# Tiny817_Xplained_Pro_EDBG.net
KiCad netlist of a schematic drawn in Altium Designer
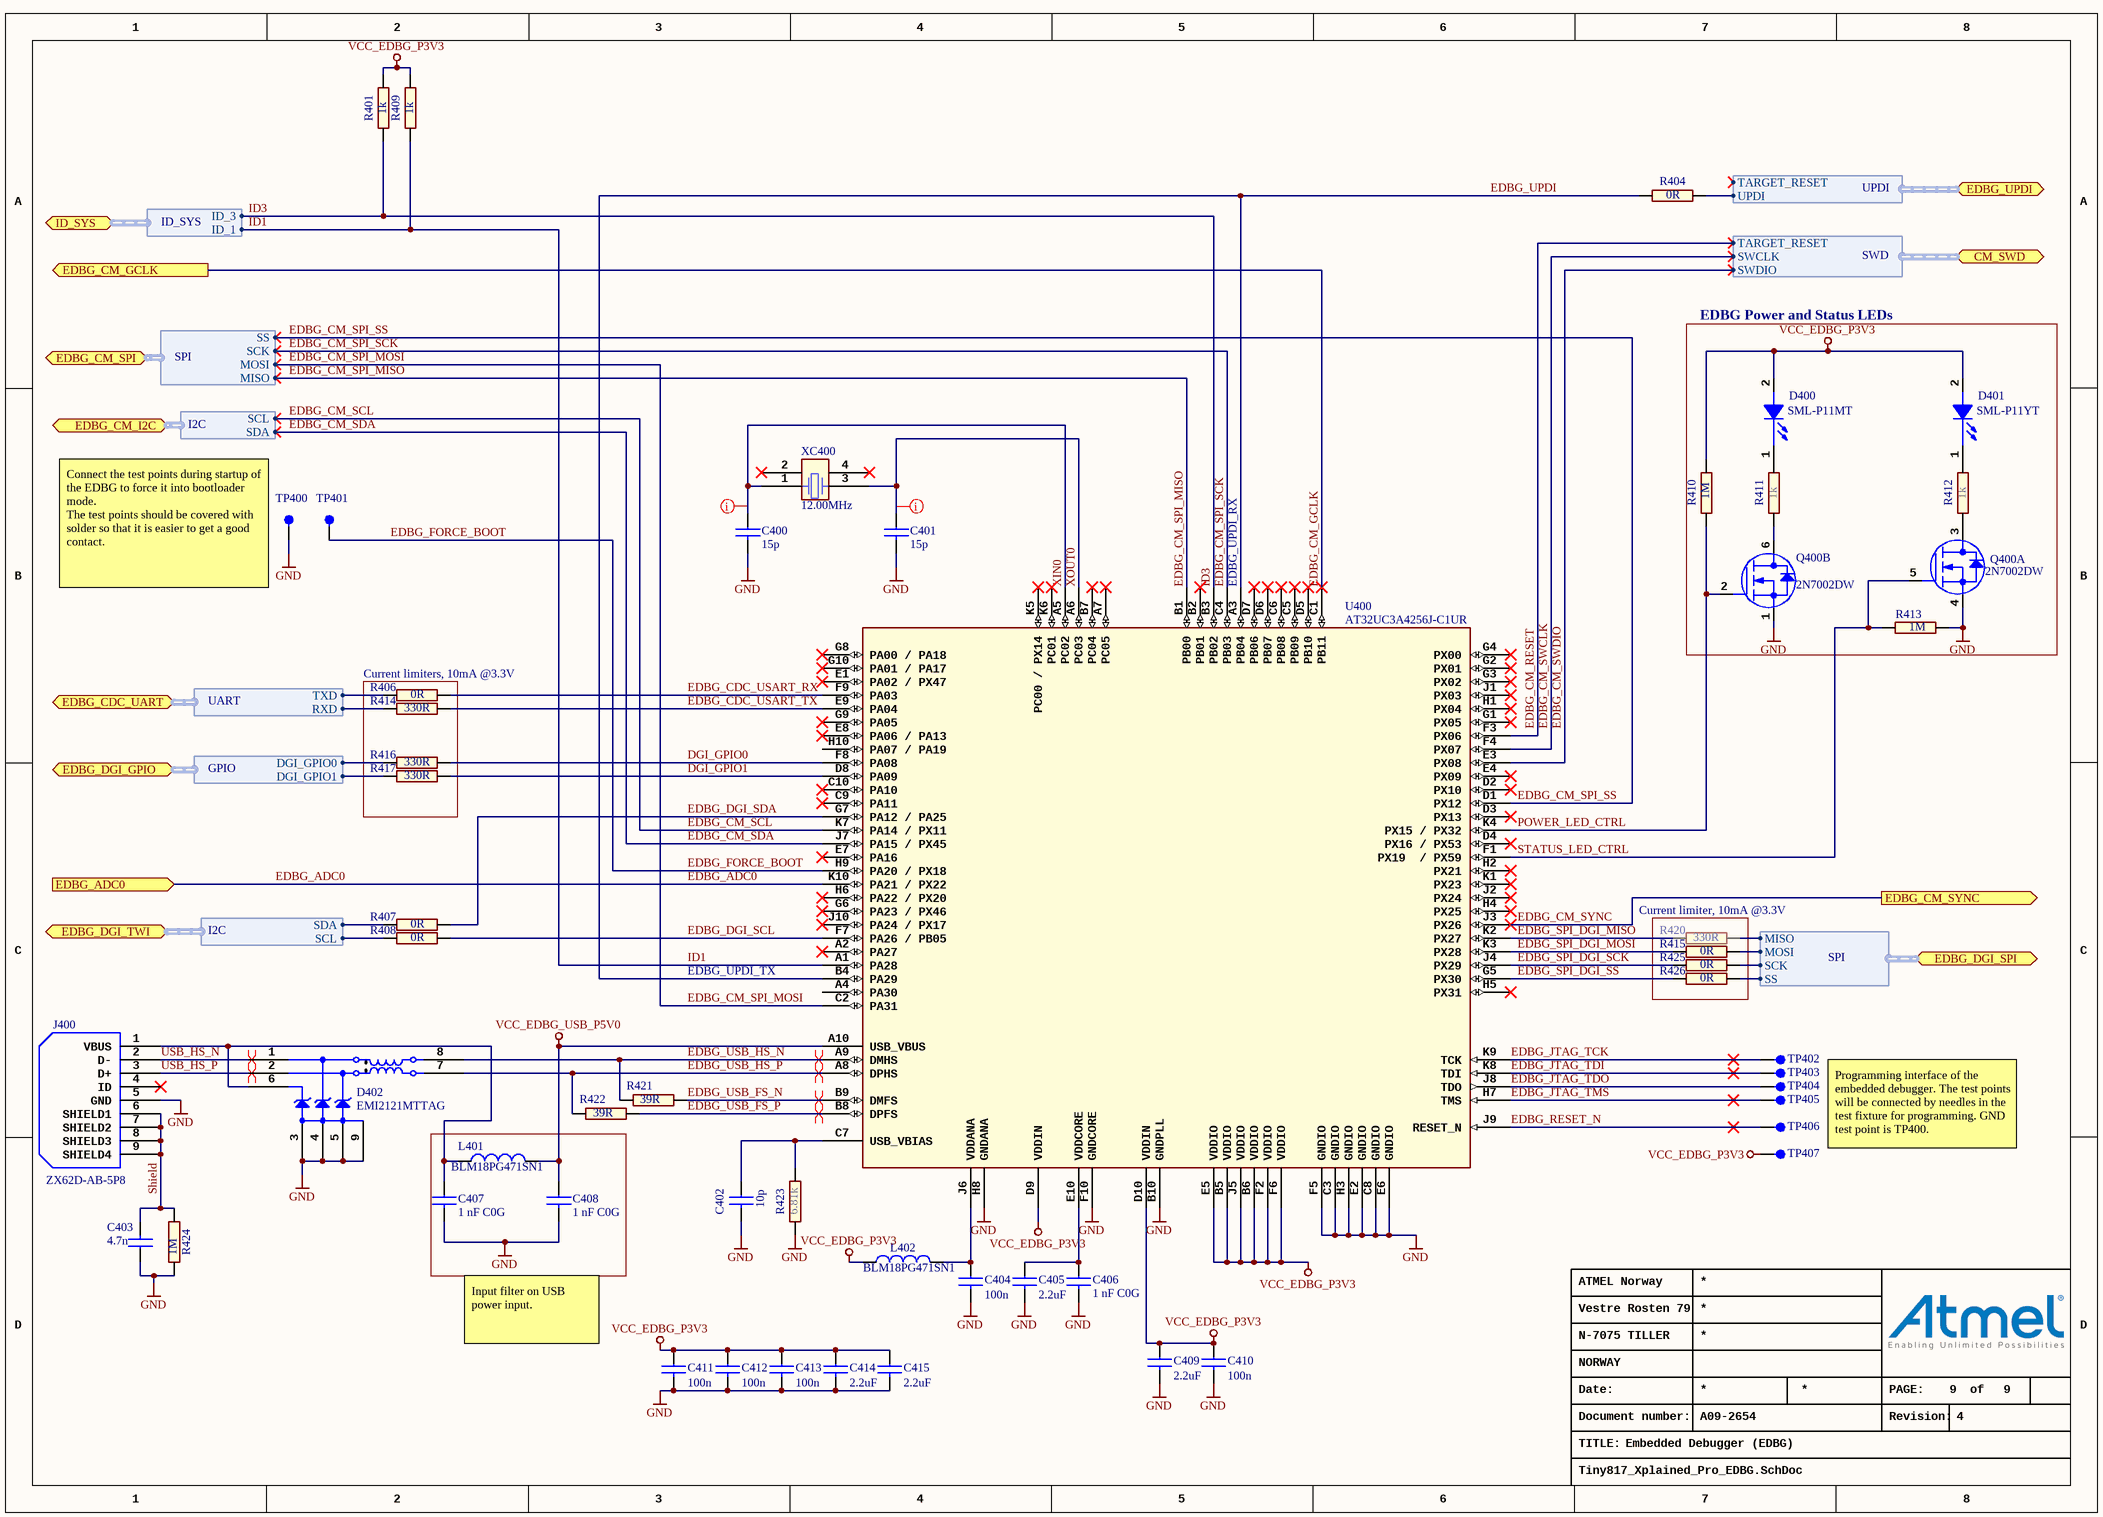
[diagram p0: Tiny817_Xplained_Pro_EDBG.SchDoc]

(export (version "E")
  (design (tool "Eeschema 10.0.6"))
  (components
    (comp (ref "C400")
      (value "15p")
      (footprint "AP1-00053")
      (description "Ceramic capacitor, SMD 0402, NP0, 50V, +/-5%")
      (fields (field (name "TOLERANCE") "50V, +/-5%") (field (name "MANUFACTURER") "AVX"))
      (libsource (lib "AltiumDbLib") (part "CAP-NONPOL"))
    )
    (comp (ref "C401")
      (value "15p")
      (footprint "AP1-00053")
      (description "Ceramic capacitor, SMD 0402, NP0, 50V, +/-5%")
      (fields (field (name "TOLERANCE") "50V, +/-5%") (field (name "MANUFACTURER") "AVX"))
      (libsource (lib "AltiumDbLib") (part "CAP-NONPOL"))
    )
    (comp (ref "C402")
      (value "10p")
      (footprint "AP1-00053")
      (description "Ceramic capacitor, SMD 0402, NP0, 50V, +/-5%")
      (fields (field (name "TOLERANCE") "50V, +/-5%") (field (name "MANUFACTURER") "AVX"))
      (libsource (lib "AltiumDbLib") (part "CAP-NONPOL"))
    )
    (comp (ref "C403")
      (value "4.7n")
      (footprint "AP1-00053")
      (description "Ceramic capacitor, SMD 0402, X7R, 25V, +/-10%")
      (fields (field (name "TOLERANCE") "25V, +/-10%") (field (name "MANUFACTURER") "PHYCOMP"))
      (libsource (lib "AltiumDbLib") (part "CAP-NONPOL"))
    )
    (comp (ref "C404")
      (value "100n")
      (footprint "AP1-00053")
      (description "Ceramic capacitor, SMD 0402, X7R, 16V, +/-10%")
      (fields (field (name "TOLERANCE") "16V, +/-10%") (field (name "MANUFACTURER") "Kemet"))
      (libsource (lib "AltiumDbLib") (part "CAP-NONPOL"))
    )
    (comp (ref "C405")
      (value "2.2uF")
      (footprint "AP1-00053")
      (description "Ceramic capacitor, SMD 0402, X5R, 6.3V, +/-20%")
      (fields (field (name "TOLERANCE") "Â±20%") (field (name "MANUFACTURER") "Kemet"))
      (libsource (lib "AltiumDbLib") (part "CAP-NONPOL"))
    )
    (comp (ref "C406")
      (value "1 nF C0G")
      (footprint "AP1-00053")
      (description "Ceramic capacitor, SMD 0402, C0G, 50V, +/-5%")
      (fields (field (name "TOLERANCE") "5%") (field (name "MANUFACTURER") "Murata"))
      (libsource (lib "AltiumDbLib") (part "CAP-NONPOL"))
    )
    (comp (ref "C407")
      (value "1 nF C0G")
      (footprint "AP1-00053")
      (description "Ceramic capacitor, SMD 0402, C0G, 50V, +/-5%")
      (fields (field (name "TOLERANCE") "5%") (field (name "MANUFACTURER") "Murata"))
      (libsource (lib "AltiumDbLib") (part "CAP-NONPOL"))
    )
    (comp (ref "C408")
      (value "1 nF C0G")
      (footprint "AP1-00053")
      (description "Ceramic capacitor, SMD 0402, C0G, 50V, +/-5%")
      (fields (field (name "TOLERANCE") "5%") (field (name "MANUFACTURER") "Murata"))
      (libsource (lib "AltiumDbLib") (part "CAP-NONPOL"))
    )
    (comp (ref "C409")
      (value "2.2uF")
      (footprint "AP1-00053")
      (description "Ceramic capacitor, SMD 0402, X5R, 6.3V, +/-20%")
      (fields (field (name "TOLERANCE") "Â±20%") (field (name "MANUFACTURER") "Kemet"))
      (libsource (lib "AltiumDbLib") (part "CAP-NONPOL"))
    )
    (comp (ref "C410")
      (value "100n")
      (footprint "AP1-00053")
      (description "Ceramic capacitor, SMD 0402, X7R, 16V, +/-10%")
      (fields (field (name "TOLERANCE") "16V, +/-10%") (field (name "MANUFACTURER") "Kemet"))
      (libsource (lib "AltiumDbLib") (part "CAP-NONPOL"))
    )
    (comp (ref "C411")
      (value "100n")
      (footprint "AP1-00053")
      (description "Ceramic capacitor, SMD 0402, X7R, 16V, +/-10%")
      (fields (field (name "TOLERANCE") "16V, +/-10%") (field (name "MANUFACTURER") "Kemet"))
      (libsource (lib "AltiumDbLib") (part "CAP-NONPOL"))
    )
    (comp (ref "C412")
      (value "100n")
      (footprint "AP1-00053")
      (description "Ceramic capacitor, SMD 0402, X7R, 16V, +/-10%")
      (fields (field (name "TOLERANCE") "16V, +/-10%") (field (name "MANUFACTURER") "Kemet"))
      (libsource (lib "AltiumDbLib") (part "CAP-NONPOL"))
    )
    (comp (ref "C413")
      (value "100n")
      (footprint "AP1-00053")
      (description "Ceramic capacitor, SMD 0402, X7R, 16V, +/-10%")
      (fields (field (name "TOLERANCE") "16V, +/-10%") (field (name "MANUFACTURER") "Kemet"))
      (libsource (lib "AltiumDbLib") (part "CAP-NONPOL"))
    )
    (comp (ref "C414")
      (value "2.2uF")
      (footprint "AP1-00053")
      (description "Ceramic capacitor, SMD 0402, X5R, 6.3V, +/-20%")
      (fields (field (name "TOLERANCE") "Â±20%") (field (name "MANUFACTURER") "Kemet"))
      (libsource (lib "AltiumDbLib") (part "CAP-NONPOL"))
    )
    (comp (ref "C415")
      (value "2.2uF")
      (footprint "AP1-00053")
      (description "Ceramic capacitor, SMD 0402, X5R, 6.3V, +/-20%")
      (fields (field (name "TOLERANCE") "Â±20%") (field (name "MANUFACTURER") "Kemet"))
      (libsource (lib "AltiumDbLib") (part "CAP-NONPOL"))
    )
    (comp (ref "D400")
      (value "SML-P11MT")
      (footprint "AP4-00160")
      (description "LED, SMD 0402, Green, Wave length=569nm, 2.1mcd @ (1mA, 1.9Vf)")
      (fields (field (name "MANUFACTURER") "ROHM") (field (name "MPN") "SML-P11MT-T86"))
      (libsource (lib "AltiumDbLib") (part "LED_12"))
    )
    (comp (ref "D401")
      (value "SML-P11YT")
      (footprint "AP4-00160")
      (description "LED, SMD 0402, Yellow, Wave length=586nm, 7.6mcd @ (1mA, 1.9Vf)")
      (fields (field (name "MANUFACTURER") "ROHM") (field (name "MPN") "SML-P11YT-T86"))
      (libsource (lib "AltiumDbLib") (part "LED_12"))
    )
    (comp (ref "D402")
      (value "EMI2121MTTAG")
      (footprint "AP4-00159")
      (description "EMI2121, SZEMI2121 Single Pair Common Mode Filter with ESD Protection")
      (fields (field (name "MANUFACTURER") "ON Semiconductor"))
      (libsource (lib "AltiumDbLib") (part "EMI2121"))
    )
    (comp (ref "J400")
      (value "ZX62D-AB-5P8")
      (footprint "AP8-00852")
      (description "Micro USB AB Connector, Standard SMT + DIP")
      (fields (field (name "MANUFACTURER") "HIROSE") (field (name "MPN") "ZX62D-AB-5P8(30)"))
      (libsource (lib "AltiumDbLib") (part "USB_AB"))
    )
    (comp (ref "L401")
      (value "BLM18PG471SN1")
      (footprint "AP3-00005")
      (description "SMD RF inductor 0603. Z=470Ohm (@100MHz), Max R(dc)=0.65Ohm, Max current=1A")
      (fields (field (name "MANUFACTURER") "Murata"))
      (libsource (lib "AltiumDbLib") (part "INDUCTOR"))
    )
    (comp (ref "L402")
      (value "BLM18PG471SN1")
      (footprint "AP3-00005")
      (description "SMD RF inductor 0603. Z=470Ohm (@100MHz), Max R(dc)=0.65Ohm, Max current=1A")
      (fields (field (name "MANUFACTURER") "Murata"))
      (libsource (lib "AltiumDbLib") (part "INDUCTOR"))
    )
    (comp (ref "Q400")
      (value "2N7002DW")
      (footprint "AP5-00001")
      (description "Dual N-Channel MOSFET, 60V, 115mA cont,RDS(ON) < 7.5 Ohm @50mA@5V, SOT-363")
      (fields
        (field (name "MANUFACTURER") "Fairchild")
        (field (name "Comment") "Same as 2N7002 but with two MOSFETs in one package")
      )
      (libsource (lib "AltiumDbLib") (part "MOSFET_DUAL_N_S2G2D1S1G1D2"))
    )
    (comp (ref "R401")
      (value "1k")
      (footprint "AP2-00000")
      (description "Thick film resistor, SMD 0402, 1/16W, 1%")
      (fields (field (name "TOLERANCE") "1 %") (field (name "MANUFACTURER") "ASJ"))
      (libsource (lib "AltiumDbLib") (part "R2"))
    )
    (comp (ref "R404")
      (value "0R")
      (footprint "AP2-00000")
      (description "RES 0.0 OHM 1/16W 0402 SMD")
      (fields (field (name "TOLERANCE") "1 %") (field (name "MANUFACTURER") "(n/a)"))
      (libsource (lib "") (part "R2_1"))
    )
    (comp (ref "R406")
      (value "0R")
      (footprint "AP2-00000")
      (description "RES 0.0 OHM 1/16W 0402 SMD")
      (fields (field (name "TOLERANCE") "1 %") (field (name "MANUFACTURER") "(n/a)"))
      (libsource (lib "") (part "R2_1"))
    )
    (comp (ref "R407")
      (value "0R")
      (footprint "AP2-00000")
      (description "RES 0.0 OHM 1/16W 0402 SMD")
      (fields (field (name "TOLERANCE") "1 %") (field (name "MANUFACTURER") "(n/a)"))
      (libsource (lib "") (part "R2_1"))
    )
    (comp (ref "R408")
      (value "0R")
      (footprint "AP2-00000")
      (description "RES 0.0 OHM 1/16W 0402 SMD")
      (fields (field (name "TOLERANCE") "1 %") (field (name "MANUFACTURER") "(n/a)"))
      (libsource (lib "") (part "R2_1"))
    )
    (comp (ref "R409")
      (value "1k")
      (footprint "AP2-00000")
      (description "Thick film resistor, SMD 0402, 1/16W, 1%")
      (fields (field (name "TOLERANCE") "1 %") (field (name "MANUFACTURER") "ASJ"))
      (libsource (lib "AltiumDbLib") (part "R2"))
    )
    (comp (ref "R410")
      (value "1M")
      (footprint "AP2-00011")
      (description "Thick film resistor, SMD 0402, 1/16W, 1%")
      (fields (field (name "TOLERANCE") "1 %") (field (name "MANUFACTURER") "ASJ"))
      (libsource (lib "AltiumDbLib") (part "R2"))
    )
    (comp (ref "R411")
      (value "1k")
      (footprint "AP2-00011")
      (description "Thick film resistor, SMD 0402, 1/16W, 1%")
      (fields (field (name "TOLERANCE") "1 %") (field (name "MANUFACTURER") "ASJ"))
      (libsource (lib "AltiumDbLib") (part "R2"))
    )
    (comp (ref "R412")
      (value "1k")
      (footprint "AP2-00011")
      (description "Thick film resistor, SMD 0402, 1/16W, 1%")
      (fields (field (name "TOLERANCE") "1 %") (field (name "MANUFACTURER") "ASJ"))
      (libsource (lib "AltiumDbLib") (part "R2"))
    )
    (comp (ref "R413")
      (value "1M")
      (footprint "AP2-00011")
      (description "Thick film resistor, SMD 0402, 1/16W, 1%")
      (fields (field (name "TOLERANCE") "1 %") (field (name "MANUFACTURER") "ASJ"))
      (libsource (lib "") (part "R2_1"))
    )
    (comp (ref "R414")
      (value "330R")
      (footprint "AP2-00000")
      (description "Thick film resistor, SMD 0402, 1/16W, 1%")
      (fields (field (name "TOLERANCE") "1 %") (field (name "MANUFACTURER") "ASJ"))
      (libsource (lib "") (part "R2_2"))
    )
    (comp (ref "R415")
      (value "0R")
      (footprint "AP2-00000")
      (description "RES 0.0 OHM 1/16W 0402 SMD")
      (fields (field (name "TOLERANCE") "1 %") (field (name "MANUFACTURER") "(n/a)"))
      (libsource (lib "") (part "R2_1"))
    )
    (comp (ref "R416")
      (value "330R")
      (footprint "AP2-00000")
      (description "Thick film resistor, SMD 0402, 1/16W, 1%")
      (fields (field (name "TOLERANCE") "1 %") (field (name "MANUFACTURER") "ASJ"))
      (libsource (lib "") (part "R2_2"))
    )
    (comp (ref "R417")
      (value "330R")
      (footprint "AP2-00000")
      (description "Thick film resistor, SMD 0402, 1/16W, 1%")
      (fields (field (name "TOLERANCE") "1 %") (field (name "MANUFACTURER") "ASJ"))
      (libsource (lib "") (part "R2_2"))
    )
    (comp (ref "R420")
      (value "330R")
      (footprint "AP2-00000")
      (description "Thick film resistor, SMD 0402, 1/16W, 1%")
      (fields (field (name "TOLERANCE") "1 %") (field (name "MANUFACTURER") "ASJ"))
      (libsource (lib "") (part "R2_2"))
    )
    (comp (ref "R421")
      (value "39R")
      (footprint "AP2-00011")
      (description "Thick film resistor, SMD 0402, 1/16W, 1%")
      (fields (field (name "TOLERANCE") "1 %") (field (name "MANUFACTURER") "ASJ"))
      (libsource (lib "") (part "R2_3"))
    )
    (comp (ref "R422")
      (value "39R")
      (footprint "AP2-00011")
      (description "Thick film resistor, SMD 0402, 1/16W, 1%")
      (fields (field (name "TOLERANCE") "1 %") (field (name "MANUFACTURER") "ASJ"))
      (libsource (lib "") (part "R2_3"))
    )
    (comp (ref "R423")
      (value "6.81k")
      (footprint "AP2-00011")
      (description "Thick film resistor, SMD 0402, 1/16W, 1%")
      (fields (field (name "TOLERANCE") "1%") (field (name "MANUFACTURER") "vishay"))
      (libsource (lib "AltiumDbLib") (part "R2"))
    )
    (comp (ref "R424")
      (value "1M")
      (footprint "AP2-00011")
      (description "Thick film resistor, SMD 0402, 1/16W, 1%")
      (fields (field (name "TOLERANCE") "1 %") (field (name "MANUFACTURER") "ASJ"))
      (libsource (lib "") (part "R2_4"))
    )
    (comp (ref "R425")
      (value "0R")
      (footprint "AP2-00000")
      (description "RES 0.0 OHM 1/16W 0402 SMD")
      (fields (field (name "TOLERANCE") "1 %") (field (name "MANUFACTURER") "(n/a)"))
      (libsource (lib "") (part "R2_1"))
    )
    (comp (ref "R426")
      (value "0R")
      (footprint "AP2-00000")
      (description "RES 0.0 OHM 1/16W 0402 SMD")
      (fields (field (name "TOLERANCE") "1 %") (field (name "MANUFACTURER") "(n/a)"))
      (libsource (lib "") (part "R2_1"))
    )
    (comp (ref "TP400")
      (value "~")
      (footprint "AP8-00010")
      (description "Single SMD testpad")
      (libsource (lib "AltiumDbLib") (part "TESTPOINT"))
    )
    (comp (ref "TP401")
      (value "~")
      (footprint "AP8-00010")
      (description "Single SMD testpad")
      (libsource (lib "AltiumDbLib") (part "TESTPOINT"))
    )
    (comp (ref "TP402")
      (value "~")
      (footprint "AP8-00010")
      (description "Single SMD testpad")
      (libsource (lib "AltiumDbLib") (part "TESTPOINT"))
    )
    (comp (ref "TP403")
      (value "~")
      (footprint "AP8-00010")
      (description "Single SMD testpad")
      (libsource (lib "AltiumDbLib") (part "TESTPOINT"))
    )
    (comp (ref "TP404")
      (value "~")
      (footprint "AP8-00010")
      (description "Single SMD testpad")
      (libsource (lib "AltiumDbLib") (part "TESTPOINT"))
    )
    (comp (ref "TP405")
      (value "~")
      (footprint "AP8-00010")
      (description "Single SMD testpad")
      (libsource (lib "AltiumDbLib") (part "TESTPOINT"))
    )
    (comp (ref "TP406")
      (value "~")
      (footprint "AP8-00010")
      (description "Single SMD testpad")
      (libsource (lib "AltiumDbLib") (part "TESTPOINT"))
    )
    (comp (ref "TP407")
      (value "~")
      (footprint "AP8-00010")
      (description "Single SMD testpad")
      (libsource (lib "AltiumDbLib") (part "TESTPOINT"))
    )
    (comp (ref "U400")
      (value "AT32UC3A4256J-C1UR")
      (footprint "AP6-00206")
      (description "AVR 32-bit RISC MCU")
      (fields (field (name "MANUFACTURER") "ATMEL") (field (name "Comment") "100 ball VFBGA"))
      (libsource (lib "AltiumDbLib") (part "AT32UC3A4_VFBGA"))
    )
    (comp (ref "XC400")
      (value "12.00MHz")
      (footprint "AP7-00089")
      (description "Kyocera CX3225GB12000H0KPSC1, 12MHz, 12pF, SMD crystal")
      (fields
        (field (name "TOLERANCE") "Â±30ppm")
        (field (name "MANUFACTURER") "Kyocera Crystal Device Corporation")
      )
      (libsource (lib "AltiumDbLib") (part "CRYSTAL1324"))
    )
  )
  (nets
    (net (code "7") (name "/DGI_GPIO0") (class "Default")
      (node (ref "R416") (pin "2") (pinfunction "2_2") (pintype "passive"))
      (node (ref "U400") (pin "F8") (pinfunction "PA08_F8") (pintype "bidirectional"))
    )
    (net (code "8") (name "/DGI_GPIO1") (class "Default")
      (node (ref "R417") (pin "2") (pinfunction "2_2") (pintype "passive"))
      (node (ref "U400") (pin "D8") (pinfunction "PA09_D8") (pintype "bidirectional"))
    )
    (net (code "9") (name "/EDBG_ADC0") (class "Default")
      (node (ref "U400") (pin "K10") (pinfunction "PA21_/_PX22_K10") (pintype "bidirectional"))
    )
    (net (code "10") (name "/EDBG_CDC_USART_RX") (class "Default")
      (node (ref "R406") (pin "1") (pinfunction "1_1") (pintype "passive"))
      (node (ref "U400") (pin "F9") (pinfunction "PA03_F9") (pintype "bidirectional"))
    )
    (net (code "11") (name "/EDBG_CDC_USART_TX") (class "Default")
      (node (ref "R414") (pin "2") (pinfunction "2_2") (pintype "passive"))
      (node (ref "U400") (pin "E9") (pinfunction "PA04_E9") (pintype "bidirectional"))
    )
    (net (code "12") (name "/EDBG_CM_GCLK") (class "Default")
      (node (ref "U400") (pin "C1") (pinfunction "PB11_C1") (pintype "bidirectional+no_connect"))
    )
    (net (code "13") (name "/EDBG_CM_RESET") (class "Default")
      (node (ref "U400") (pin "F3") (pinfunction "PX06_F3") (pintype "bidirectional+no_connect"))
    )
    (net (code "14") (name "/EDBG_CM_SCL") (class "Default")
      (node (ref "U400") (pin "K7") (pinfunction "PA14_/_PX11_K7") (pintype "bidirectional+no_connect"))
    )
    (net (code "15") (name "/EDBG_CM_SDA") (class "Default")
      (node (ref "U400") (pin "J7") (pinfunction "PA15_/_PX45_J7") (pintype "bidirectional+no_connect"))
    )
    (net (code "16") (name "/EDBG_CM_SPI_MISO") (class "Default")
      (node (ref "U400") (pin "B1") (pinfunction "PB00_B1") (pintype "bidirectional+no_connect"))
    )
    (net (code "17") (name "/EDBG_CM_SPI_MOSI") (class "Default")
      (node (ref "U400") (pin "C2") (pinfunction "PA31_C2") (pintype "bidirectional+no_connect"))
    )
    (net (code "18") (name "/EDBG_CM_SPI_SCK") (class "Default")
      (node (ref "U400") (pin "C4") (pinfunction "PB03_C4") (pintype "bidirectional+no_connect"))
    )
    (net (code "19") (name "/EDBG_CM_SPI_SS") (class "Default")
      (node (ref "U400") (pin "D1") (pinfunction "PX12_D1") (pintype "bidirectional+no_connect"))
    )
    (net (code "20") (name "/EDBG_CM_SWCLK") (class "Default")
      (node (ref "U400") (pin "F4") (pinfunction "PX07_F4") (pintype "bidirectional+no_connect"))
    )
    (net (code "21") (name "/EDBG_CM_SWDIO") (class "Default")
      (node (ref "U400") (pin "E3") (pinfunction "PX08_E3") (pintype "bidirectional+no_connect"))
    )
    (net (code "22") (name "/EDBG_CM_SYNC") (class "Default")
      (node (ref "U400") (pin "J3") (pinfunction "PX26_J3") (pintype "bidirectional+no_connect"))
    )
    (net (code "23") (name "/EDBG_DGI_SCL") (class "Default")
      (node (ref "R408") (pin "1") (pinfunction "1_1") (pintype "passive"))
      (node (ref "U400") (pin "F7") (pinfunction "PA26_/_PB05_F7") (pintype "bidirectional"))
    )
    (net (code "24") (name "/EDBG_DGI_SDA") (class "Default")
      (node (ref "R407") (pin "1") (pinfunction "1_1") (pintype "passive"))
      (node (ref "U400") (pin "G7") (pinfunction "PA12_/_PA25_G7") (pintype "bidirectional"))
    )
    (net (code "25") (name "/EDBG_FORCE_BOOT") (class "Default")
      (node (ref "TP401") (pin "1") (pinfunction "1_1") (pintype "passive"))
      (node (ref "U400") (pin "H9") (pinfunction "PA20_/_PX18_H9") (pintype "bidirectional"))
    )
    (net (code "26") (name "/EDBG_JTAG_TCK") (class "Default")
      (node (ref "TP402") (pin "1") (pinfunction "1_1") (pintype "passive"))
      (node (ref "U400") (pin "K9") (pinfunction "TCK_K9") (pintype "input"))
    )
    (net (code "27") (name "/EDBG_JTAG_TDI") (class "Default")
      (node (ref "TP403") (pin "1") (pinfunction "1_1") (pintype "passive"))
      (node (ref "U400") (pin "K8") (pinfunction "TDI_K8") (pintype "input"))
    )
    (net (code "28") (name "/EDBG_JTAG_TDO") (class "Default")
      (node (ref "TP404") (pin "1") (pinfunction "1_1") (pintype "passive"))
      (node (ref "U400") (pin "J8") (pinfunction "TDO_J8") (pintype "output"))
    )
    (net (code "29") (name "/EDBG_JTAG_TMS") (class "Default")
      (node (ref "TP405") (pin "1") (pinfunction "1_1") (pintype "passive"))
      (node (ref "U400") (pin "H7") (pinfunction "TMS_H7") (pintype "input"))
    )
    (net (code "30") (name "/EDBG_RESET_N") (class "Default")
      (node (ref "TP406") (pin "1") (pinfunction "1_1") (pintype "passive"))
      (node (ref "U400") (pin "J9") (pinfunction "RESET_N_J9") (pintype "input"))
    )
    (net (code "31") (name "/EDBG_SPI_DGI_MISO") (class "Default")
      (node (ref "R420") (pin "1") (pinfunction "1_1") (pintype "passive"))
      (node (ref "U400") (pin "K2") (pinfunction "PX27_K2") (pintype "bidirectional"))
    )
    (net (code "32") (name "/EDBG_SPI_DGI_MOSI") (class "Default")
      (node (ref "R415") (pin "2") (pinfunction "2_2") (pintype "passive"))
      (node (ref "U400") (pin "K3") (pinfunction "PX28_K3") (pintype "bidirectional"))
    )
    (net (code "33") (name "/EDBG_SPI_DGI_SCK") (class "Default")
      (node (ref "R425") (pin "2") (pinfunction "2_2") (pintype "passive"))
      (node (ref "U400") (pin "J4") (pinfunction "PX29_J4") (pintype "bidirectional"))
    )
    (net (code "34") (name "/EDBG_SPI_DGI_SS") (class "Default")
      (node (ref "R426") (pin "2") (pinfunction "2_2") (pintype "passive"))
      (node (ref "U400") (pin "G5") (pinfunction "PX30_G5") (pintype "bidirectional"))
    )
    (net (code "35") (name "/EDBG_UPDI") (class "Default")
      (node (ref "R404") (pin "2") (pinfunction "2_2") (pintype "passive"))
      (node (ref "U400") (pin "A3") (pinfunction "PB04_A3") (pintype "bidirectional"))
      (node (ref "U400") (pin "B4") (pinfunction "PA29_B4") (pintype "bidirectional"))
    )
    (net (code "36") (name "/EDBG_USB_FS_N") (class "Default")
      (node (ref "R421") (pin "2") (pinfunction "2_2") (pintype "passive"))
      (node (ref "U400") (pin "B9") (pinfunction "DMFS_B9") (pintype "bidirectional"))
    )
    (net (code "37") (name "/EDBG_USB_FS_P") (class "Default")
      (node (ref "R422") (pin "2") (pinfunction "2_2") (pintype "passive"))
      (node (ref "U400") (pin "B8") (pinfunction "DPFS_B8") (pintype "bidirectional"))
    )
    (net (code "38") (name "/EDBG_USB_HS_N") (class "Default")
      (node (ref "D402") (pin "8") (pinfunction "DIFF1_INT_8") (pintype "passive"))
      (node (ref "R421") (pin "1") (pinfunction "1_1") (pintype "passive"))
      (node (ref "U400") (pin "A9") (pinfunction "DMHS_A9") (pintype "bidirectional"))
    )
    (net (code "39") (name "/EDBG_USB_HS_P") (class "Default")
      (node (ref "D402") (pin "7") (pinfunction "DIFF2_INT_7") (pintype "passive"))
      (node (ref "R422") (pin "1") (pinfunction "1_1") (pintype "passive"))
      (node (ref "U400") (pin "A8") (pinfunction "DPHS_A8") (pintype "bidirectional"))
    )
    (net (code "40") (name "/ID1") (class "Default")
      (node (ref "R409") (pin "1") (pinfunction "1_1") (pintype "passive"))
      (node (ref "U400") (pin "A1") (pinfunction "PA28_A1") (pintype "bidirectional"))
    )
    (net (code "41") (name "/ID3") (class "Default")
      (node (ref "R401") (pin "1") (pinfunction "1_1") (pintype "passive"))
      (node (ref "U400") (pin "B3") (pinfunction "PB02_B3") (pintype "bidirectional"))
    )
    (net (code "42") (name "/POWER_LED_CTRL") (class "Default")
      (node (ref "Q400") (pin "2") (pinfunction "G2_2") (pintype "passive"))
      (node (ref "R410") (pin "1") (pinfunction "1_1") (pintype "passive"))
      (node (ref "U400") (pin "K4") (pinfunction "PX15_/_PX32_K4") (pintype "bidirectional"))
    )
    (net (code "43") (name "/RXD") (class "Default")
      (node (ref "R414") (pin "1") (pinfunction "1_1") (pintype "passive"))
    )
    (net (code "44") (name "/STATUS_LED_CTRL") (class "Default")
      (node (ref "Q400") (pin "5") (pinfunction "G1_5") (pintype "passive"))
      (node (ref "R413") (pin "2") (pinfunction "2_2") (pintype "passive"))
      (node (ref "U400") (pin "F1") (pinfunction "PX19__/_PX59_F1") (pintype "bidirectional"))
    )
    (net (code "45") (name "/Shield") (class "Default")
      (node (ref "C403") (pin "2") (pinfunction "2_2") (pintype "passive"))
      (node (ref "J400") (pin "6") (pinfunction "SHIELD1_6") (pintype "passive"))
      (node (ref "J400") (pin "7") (pinfunction "SHIELD2_7") (pintype "passive"))
      (node (ref "J400") (pin "8") (pinfunction "SHIELD3_8") (pintype "passive"))
      (node (ref "J400") (pin "9") (pinfunction "SHIELD4_9") (pintype "passive"))
      (node (ref "R424") (pin "2") (pinfunction "2_2") (pintype "passive"))
    )
    (net (code "46") (name "/TXD") (class "Default")
      (node (ref "R406") (pin "2") (pinfunction "2_2") (pintype "passive"))
    )
    (net (code "47") (name "/UPDI") (class "Default")
      (node (ref "R404") (pin "1") (pinfunction "1_1") (pintype "passive"))
    )
    (net (code "48") (name "/USB_HS_N") (class "Default")
      (node (ref "D402") (pin "1") (pinfunction "DIFF1_EXT_1") (pintype "passive"))
      (node (ref "J400") (pin "2") (pinfunction "D-_2") (pintype "passive"))
    )
    (net (code "49") (name "/USB_HS_P") (class "Default")
      (node (ref "D402") (pin "2") (pinfunction "DIFF2_EXT_2") (pintype "passive"))
      (node (ref "J400") (pin "3") (pinfunction "D+_3") (pintype "passive"))
    )
    (net (code "50") (name "/XIN0") (class "Default")
      (node (ref "C400") (pin "1") (pinfunction "1_1") (pintype "passive"))
      (node (ref "U400") (pin "A5") (pinfunction "PC02_A5") (pintype "bidirectional"))
      (node (ref "XC400") (pin "1") (pinfunction "1_1") (pintype "passive"))
    )
    (net (code "51") (name "/XOUT0") (class "Default")
      (node (ref "C401") (pin "1") (pinfunction "1_1") (pintype "passive"))
      (node (ref "U400") (pin "A6") (pinfunction "PC03_A6") (pintype "bidirectional"))
      (node (ref "XC400") (pin "3") (pinfunction "3_3") (pintype "passive"))
    )
    (net (code "59") (name "GND") (class "Default")
      (node (ref "C400") (pin "2") (pinfunction "2_2") (pintype "passive"))
      (node (ref "C401") (pin "2") (pinfunction "2_2") (pintype "passive"))
      (node (ref "C402") (pin "2") (pinfunction "2_2") (pintype "passive"))
      (node (ref "C403") (pin "1") (pinfunction "1_1") (pintype "passive"))
      (node (ref "C404") (pin "2") (pinfunction "2_2") (pintype "passive"))
      (node (ref "C405") (pin "2") (pinfunction "2_2") (pintype "passive"))
      (node (ref "C406") (pin "2") (pinfunction "2_2") (pintype "passive"))
      (node (ref "C407") (pin "2") (pinfunction "2_2") (pintype "passive"))
      (node (ref "C408") (pin "2") (pinfunction "2_2") (pintype "passive"))
      (node (ref "C409") (pin "2") (pinfunction "2_2") (pintype "passive"))
      (node (ref "C410") (pin "2") (pinfunction "2_2") (pintype "passive"))
      (node (ref "C411") (pin "2") (pinfunction "2_2") (pintype "passive"))
      (node (ref "C412") (pin "2") (pinfunction "2_2") (pintype "passive"))
      (node (ref "C413") (pin "2") (pinfunction "2_2") (pintype "passive"))
      (node (ref "C414") (pin "2") (pinfunction "2_2") (pintype "passive"))
      (node (ref "C415") (pin "2") (pinfunction "2_2") (pintype "passive"))
      (node (ref "D402") (pin "3") (pinfunction "GND_3") (pintype "power_in"))
      (node (ref "D402") (pin "4") (pinfunction "GND_4") (pintype "power_in"))
      (node (ref "D402") (pin "5") (pinfunction "GND_5") (pintype "power_in"))
      (node (ref "D402") (pin "9") (pinfunction "GND_9") (pintype "power_in"))
      (node (ref "J400") (pin "5") (pinfunction "GND_5") (pintype "passive"))
      (node (ref "Q400") (pin "1") (pinfunction "S2_1") (pintype "passive"))
      (node (ref "Q400") (pin "4") (pinfunction "S1_4") (pintype "passive"))
      (node (ref "R413") (pin "1") (pinfunction "1_1") (pintype "passive"))
      (node (ref "R423") (pin "1") (pinfunction "1_1") (pintype "passive"))
      (node (ref "R424") (pin "1") (pinfunction "1_1") (pintype "passive"))
      (node (ref "TP400") (pin "1") (pinfunction "1_1") (pintype "passive"))
      (node (ref "U400") (pin "B10") (pinfunction "GNDPLL_B10") (pintype "power_in"))
      (node (ref "U400") (pin "C3") (pinfunction "GNDIO_C3") (pintype "power_in"))
      (node (ref "U400") (pin "C8") (pinfunction "GNDIO_C8") (pintype "power_in"))
      (node (ref "U400") (pin "E2") (pinfunction "GNDIO_E2") (pintype "power_in"))
      (node (ref "U400") (pin "E6") (pinfunction "GNDIO_E6") (pintype "power_in"))
      (node (ref "U400") (pin "F10") (pinfunction "GNDCORE_F10") (pintype "power_in"))
      (node (ref "U400") (pin "F5") (pinfunction "GNDIO_F5") (pintype "power_in"))
      (node (ref "U400") (pin "H3") (pinfunction "GNDIO_H3") (pintype "power_in"))
      (node (ref "U400") (pin "H8") (pinfunction "GNDANA_H8") (pintype "power_in"))
    )
    (net (code "60") (name "Net-(D400-CATHODE)") (class "Default")
      (node (ref "D400") (pin "1") (pinfunction "CATHODE_1") (pintype "passive"))
      (node (ref "R411") (pin "2") (pinfunction "2_2") (pintype "passive"))
    )
    (net (code "61") (name "Net-(D401-CATHODE)") (class "Default")
      (node (ref "D401") (pin "1") (pinfunction "CATHODE_1") (pintype "passive"))
      (node (ref "R412") (pin "2") (pinfunction "2_2") (pintype "passive"))
    )
    (net (code "62") (name "Net-(D402-VBUS)") (class "Default")
      (node (ref "C407") (pin "1") (pinfunction "1_1") (pintype "passive"))
      (node (ref "D402") (pin "6") (pinfunction "VBUS_6") (pintype "passive"))
      (node (ref "J400") (pin "1") (pinfunction "VBUS_1") (pintype "passive"))
      (node (ref "L401") (pin "1") (pinfunction "1_1") (pintype "passive"))
    )
    (net (code "63") (name "Net-(Q400A-D1)") (class "Default")
      (node (ref "Q400") (pin "3") (pinfunction "D1_3") (pintype "passive"))
      (node (ref "R412") (pin "1") (pinfunction "1_1") (pintype "passive"))
    )
    (net (code "64") (name "Net-(Q400B-D2)") (class "Default")
      (node (ref "Q400") (pin "6") (pinfunction "D2_6") (pintype "passive"))
      (node (ref "R411") (pin "1") (pinfunction "1_1") (pintype "passive"))
    )
    (net (code "65") (name "Net-(U400-USB_VBIAS)") (class "Default")
      (node (ref "C402") (pin "1") (pinfunction "1_1") (pintype "passive"))
      (node (ref "R423") (pin "2") (pinfunction "2_2") (pintype "passive"))
      (node (ref "U400") (pin "C7") (pinfunction "USB_VBIAS_C7") (pintype "power_in"))
    )
    (net (code "66") (name "Net-(U400-VDDANA)") (class "Default")
      (node (ref "C404") (pin "1") (pinfunction "1_1") (pintype "passive"))
      (node (ref "L402") (pin "2") (pinfunction "2_2") (pintype "passive"))
      (node (ref "U400") (pin "J6") (pinfunction "VDDANA_J6") (pintype "power_in"))
    )
    (net (code "67") (name "Net-(U400-VDDCORE)") (class "Default")
      (node (ref "C405") (pin "1") (pinfunction "1_1") (pintype "passive"))
      (node (ref "C406") (pin "1") (pinfunction "1_1") (pintype "passive"))
      (node (ref "U400") (pin "E10") (pinfunction "VDDCORE_E10") (pintype "power_in"))
    )
    (net (code "68") (name "VCC_EDBG_P3V3") (class "Default")
      (node (ref "C409") (pin "1") (pinfunction "1_1") (pintype "passive"))
      (node (ref "C410") (pin "1") (pinfunction "1_1") (pintype "passive"))
      (node (ref "C411") (pin "1") (pinfunction "1_1") (pintype "passive"))
      (node (ref "C412") (pin "1") (pinfunction "1_1") (pintype "passive"))
      (node (ref "C413") (pin "1") (pinfunction "1_1") (pintype "passive"))
      (node (ref "C414") (pin "1") (pinfunction "1_1") (pintype "passive"))
      (node (ref "C415") (pin "1") (pinfunction "1_1") (pintype "passive"))
      (node (ref "D400") (pin "2") (pinfunction "ANODE_2") (pintype "passive"))
      (node (ref "D401") (pin "2") (pinfunction "ANODE_2") (pintype "passive"))
      (node (ref "L402") (pin "1") (pinfunction "1_1") (pintype "passive"))
      (node (ref "R401") (pin "2") (pinfunction "2_2") (pintype "passive"))
      (node (ref "R409") (pin "2") (pinfunction "2_2") (pintype "passive"))
      (node (ref "R410") (pin "2") (pinfunction "2_2") (pintype "passive"))
      (node (ref "TP407") (pin "1") (pinfunction "1_1") (pintype "passive"))
      (node (ref "U400") (pin "B5") (pinfunction "VDDIO_B5") (pintype "power_in"))
      (node (ref "U400") (pin "B6") (pinfunction "VDDIO_B6") (pintype "power_in"))
      (node (ref "U400") (pin "D10") (pinfunction "VDDIN_D10") (pintype "power_in"))
      (node (ref "U400") (pin "D9") (pinfunction "VDDIN_D9") (pintype "power_in"))
      (node (ref "U400") (pin "E5") (pinfunction "VDDIO_E5") (pintype "power_in"))
      (node (ref "U400") (pin "F2") (pinfunction "VDDIO_F2") (pintype "power_in"))
      (node (ref "U400") (pin "F6") (pinfunction "VDDIO_F6") (pintype "power_in"))
      (node (ref "U400") (pin "J5") (pinfunction "VDDIO_J5") (pintype "power_in"))
    )
    (net (code "69") (name "VCC_EDBG_USB_P5V0") (class "Default")
      (node (ref "C408") (pin "1") (pinfunction "1_1") (pintype "passive"))
      (node (ref "L401") (pin "2") (pinfunction "2_2") (pintype "passive"))
      (node (ref "U400") (pin "A10") (pinfunction "USB_VBUS_A10") (pintype "power_in"))
    )
    (net (code "70") (name "unconnected-(J400-ID-Pad4)") (class "Default")
      (node (ref "J400") (pin "4") (pinfunction "ID_4") (pintype "passive+no_connect"))
    )
    (net (code "71") (name "unconnected-(R407-Pad2)") (class "Default")
      (node (ref "R407") (pin "2") (pinfunction "2_2") (pintype "passive"))
    )
    (net (code "72") (name "unconnected-(R408-Pad2)") (class "Default")
      (node (ref "R408") (pin "2") (pinfunction "2_2") (pintype "passive"))
    )
    (net (code "73") (name "unconnected-(R415-Pad1)") (class "Default")
      (node (ref "R415") (pin "1") (pinfunction "1_1") (pintype "passive"))
    )
    (net (code "74") (name "unconnected-(R416-Pad1)") (class "Default")
      (node (ref "R416") (pin "1") (pinfunction "1_1") (pintype "passive"))
    )
    (net (code "75") (name "unconnected-(R417-Pad1)") (class "Default")
      (node (ref "R417") (pin "1") (pinfunction "1_1") (pintype "passive"))
    )
    (net (code "76") (name "unconnected-(R420-Pad2)") (class "Default")
      (node (ref "R420") (pin "2") (pinfunction "2_2") (pintype "passive"))
    )
    (net (code "77") (name "unconnected-(R425-Pad1)") (class "Default")
      (node (ref "R425") (pin "1") (pinfunction "1_1") (pintype "passive"))
    )
    (net (code "78") (name "unconnected-(R426-Pad1)") (class "Default")
      (node (ref "R426") (pin "1") (pinfunction "1_1") (pintype "passive"))
    )
    (net (code "79") (name "unconnected-(U400-PA00_{slash}_PA18-PadG8)") (class "Default")
      (node (ref "U400") (pin "G8") (pinfunction "PA00_/_PA18_G8") (pintype "bidirectional+no_connect"))
    )
    (net (code "80") (name "unconnected-(U400-PA01_{slash}_PA17-PadG10)") (class "Default")
      (node (ref "U400") (pin "G10") (pinfunction "PA01_/_PA17_G10") (pintype "bidirectional+no_connect"))
    )
    (net (code "81") (name "unconnected-(U400-PA02_{slash}_PX47-PadE1)") (class "Default")
      (node (ref "U400") (pin "E1") (pinfunction "PA02_/_PX47_E1") (pintype "bidirectional+no_connect"))
    )
    (net (code "82") (name "unconnected-(U400-PA05-PadG9)") (class "Default")
      (node (ref "U400") (pin "G9") (pinfunction "PA05_G9") (pintype "bidirectional+no_connect"))
    )
    (net (code "83") (name "unconnected-(U400-PA06_{slash}_PA13-PadE8)") (class "Default")
      (node (ref "U400") (pin "E8") (pinfunction "PA06_/_PA13_E8") (pintype "bidirectional+no_connect"))
    )
    (net (code "84") (name "unconnected-(U400-PA07_{slash}_PA19-PadH10)") (class "Default")
      (node (ref "U400") (pin "H10") (pinfunction "PA07_/_PA19_H10") (pintype "bidirectional"))
    )
    (net (code "85") (name "unconnected-(U400-PA10-PadC10)") (class "Default")
      (node (ref "U400") (pin "C10") (pinfunction "PA10_C10") (pintype "bidirectional+no_connect"))
    )
    (net (code "86") (name "unconnected-(U400-PA11-PadC9)") (class "Default")
      (node (ref "U400") (pin "C9") (pinfunction "PA11_C9") (pintype "bidirectional+no_connect"))
    )
    (net (code "87") (name "unconnected-(U400-PA16-PadE7)") (class "Default")
      (node (ref "U400") (pin "E7") (pinfunction "PA16_E7") (pintype "bidirectional+no_connect"))
    )
    (net (code "88") (name "unconnected-(U400-PA22_{slash}_PX20-PadH6)") (class "Default")
      (node (ref "U400") (pin "H6") (pinfunction "PA22_/_PX20_H6") (pintype "bidirectional+no_connect"))
    )
    (net (code "89") (name "unconnected-(U400-PA23_{slash}_PX46-PadG6)") (class "Default")
      (node (ref "U400") (pin "G6") (pinfunction "PA23_/_PX46_G6") (pintype "bidirectional+no_connect"))
    )
    (net (code "90") (name "unconnected-(U400-PA24_{slash}_PX17-PadJ10)") (class "Default")
      (node (ref "U400") (pin "J10") (pinfunction "PA24_/_PX17_J10") (pintype "bidirectional+no_connect"))
    )
    (net (code "91") (name "unconnected-(U400-PA27-PadA2)") (class "Default")
      (node (ref "U400") (pin "A2") (pinfunction "PA27_A2") (pintype "bidirectional+no_connect"))
    )
    (net (code "92") (name "unconnected-(U400-PA30-PadA4)") (class "Default")
      (node (ref "U400") (pin "A4") (pinfunction "PA30_A4") (pintype "bidirectional"))
    )
    (net (code "93") (name "unconnected-(U400-PB01-PadB2)") (class "Default")
      (node (ref "U400") (pin "B2") (pinfunction "PB01_B2") (pintype "bidirectional+no_connect"))
    )
    (net (code "94") (name "unconnected-(U400-PB06-PadD7)") (class "Default")
      (node (ref "U400") (pin "D7") (pinfunction "PB06_D7") (pintype "bidirectional+no_connect"))
    )
    (net (code "95") (name "unconnected-(U400-PB07-PadD6)") (class "Default")
      (node (ref "U400") (pin "D6") (pinfunction "PB07_D6") (pintype "bidirectional+no_connect"))
    )
    (net (code "96") (name "unconnected-(U400-PB08-PadC6)") (class "Default")
      (node (ref "U400") (pin "C6") (pinfunction "PB08_C6") (pintype "bidirectional+no_connect"))
    )
    (net (code "97") (name "unconnected-(U400-PB09-PadC5)") (class "Default")
      (node (ref "U400") (pin "C5") (pinfunction "PB09_C5") (pintype "bidirectional+no_connect"))
    )
    (net (code "98") (name "unconnected-(U400-PB10-PadD5)") (class "Default")
      (node (ref "U400") (pin "D5") (pinfunction "PB10_D5") (pintype "bidirectional+no_connect"))
    )
    (net (code "99") (name "unconnected-(U400-PC00_{slash}_PX14-PadK5)") (class "Default")
      (node (ref "U400") (pin "K5") (pinfunction "PC00_/_PX14_K5") (pintype "bidirectional+no_connect"))
    )
    (net (code "100") (name "unconnected-(U400-PC01-PadK6)") (class "Default")
      (node (ref "U400") (pin "K6") (pinfunction "PC01_K6") (pintype "bidirectional+no_connect"))
    )
    (net (code "101") (name "unconnected-(U400-PC04-PadB7)") (class "Default")
      (node (ref "U400") (pin "B7") (pinfunction "PC04_B7") (pintype "bidirectional+no_connect"))
    )
    (net (code "102") (name "unconnected-(U400-PC05-PadA7)") (class "Default")
      (node (ref "U400") (pin "A7") (pinfunction "PC05_A7") (pintype "bidirectional+no_connect"))
    )
    (net (code "103") (name "unconnected-(U400-PX00-PadG4)") (class "Default")
      (node (ref "U400") (pin "G4") (pinfunction "PX00_G4") (pintype "bidirectional+no_connect"))
    )
    (net (code "104") (name "unconnected-(U400-PX01-PadG2)") (class "Default")
      (node (ref "U400") (pin "G2") (pinfunction "PX01_G2") (pintype "bidirectional+no_connect"))
    )
    (net (code "105") (name "unconnected-(U400-PX02-PadG3)") (class "Default")
      (node (ref "U400") (pin "G3") (pinfunction "PX02_G3") (pintype "bidirectional+no_connect"))
    )
    (net (code "106") (name "unconnected-(U400-PX03-PadJ1)") (class "Default")
      (node (ref "U400") (pin "J1") (pinfunction "PX03_J1") (pintype "bidirectional+no_connect"))
    )
    (net (code "107") (name "unconnected-(U400-PX04-PadH1)") (class "Default")
      (node (ref "U400") (pin "H1") (pinfunction "PX04_H1") (pintype "bidirectional+no_connect"))
    )
    (net (code "108") (name "unconnected-(U400-PX05-PadG1)") (class "Default")
      (node (ref "U400") (pin "G1") (pinfunction "PX05_G1") (pintype "bidirectional+no_connect"))
    )
    (net (code "109") (name "unconnected-(U400-PX09-PadE4)") (class "Default")
      (node (ref "U400") (pin "E4") (pinfunction "PX09_E4") (pintype "bidirectional+no_connect"))
    )
    (net (code "110") (name "unconnected-(U400-PX10-PadD2)") (class "Default")
      (node (ref "U400") (pin "D2") (pinfunction "PX10_D2") (pintype "bidirectional+no_connect"))
    )
    (net (code "111") (name "unconnected-(U400-PX13-PadD3)") (class "Default")
      (node (ref "U400") (pin "D3") (pinfunction "PX13_D3") (pintype "bidirectional+no_connect"))
    )
    (net (code "112") (name "unconnected-(U400-PX16_{slash}_PX53-PadD4)") (class "Default")
      (node (ref "U400") (pin "D4") (pinfunction "PX16_/_PX53_D4") (pintype "bidirectional+no_connect"))
    )
    (net (code "113") (name "unconnected-(U400-PX21-PadH2)") (class "Default")
      (node (ref "U400") (pin "H2") (pinfunction "PX21_H2") (pintype "bidirectional+no_connect"))
    )
    (net (code "114") (name "unconnected-(U400-PX23-PadK1)") (class "Default")
      (node (ref "U400") (pin "K1") (pinfunction "PX23_K1") (pintype "bidirectional+no_connect"))
    )
    (net (code "115") (name "unconnected-(U400-PX24-PadJ2)") (class "Default")
      (node (ref "U400") (pin "J2") (pinfunction "PX24_J2") (pintype "bidirectional+no_connect"))
    )
    (net (code "116") (name "unconnected-(U400-PX25-PadH4)") (class "Default")
      (node (ref "U400") (pin "H4") (pinfunction "PX25_H4") (pintype "bidirectional+no_connect"))
    )
    (net (code "117") (name "unconnected-(U400-PX31-PadH5)") (class "Default")
      (node (ref "U400") (pin "H5") (pinfunction "PX31_H5") (pintype "bidirectional+no_connect"))
    )
    (net (code "118") (name "unconnected-(XC400-Pad2)") (class "Default")
      (node (ref "XC400") (pin "2") (pinfunction "2_2") (pintype "passive+no_connect"))
    )
    (net (code "119") (name "unconnected-(XC400-Pad4)") (class "Default")
      (node (ref "XC400") (pin "4") (pinfunction "4_4") (pintype "passive+no_connect"))
    )
  )
)
